# MotorController.net
KiCad netlist of a schematic drawn in Altium Designer
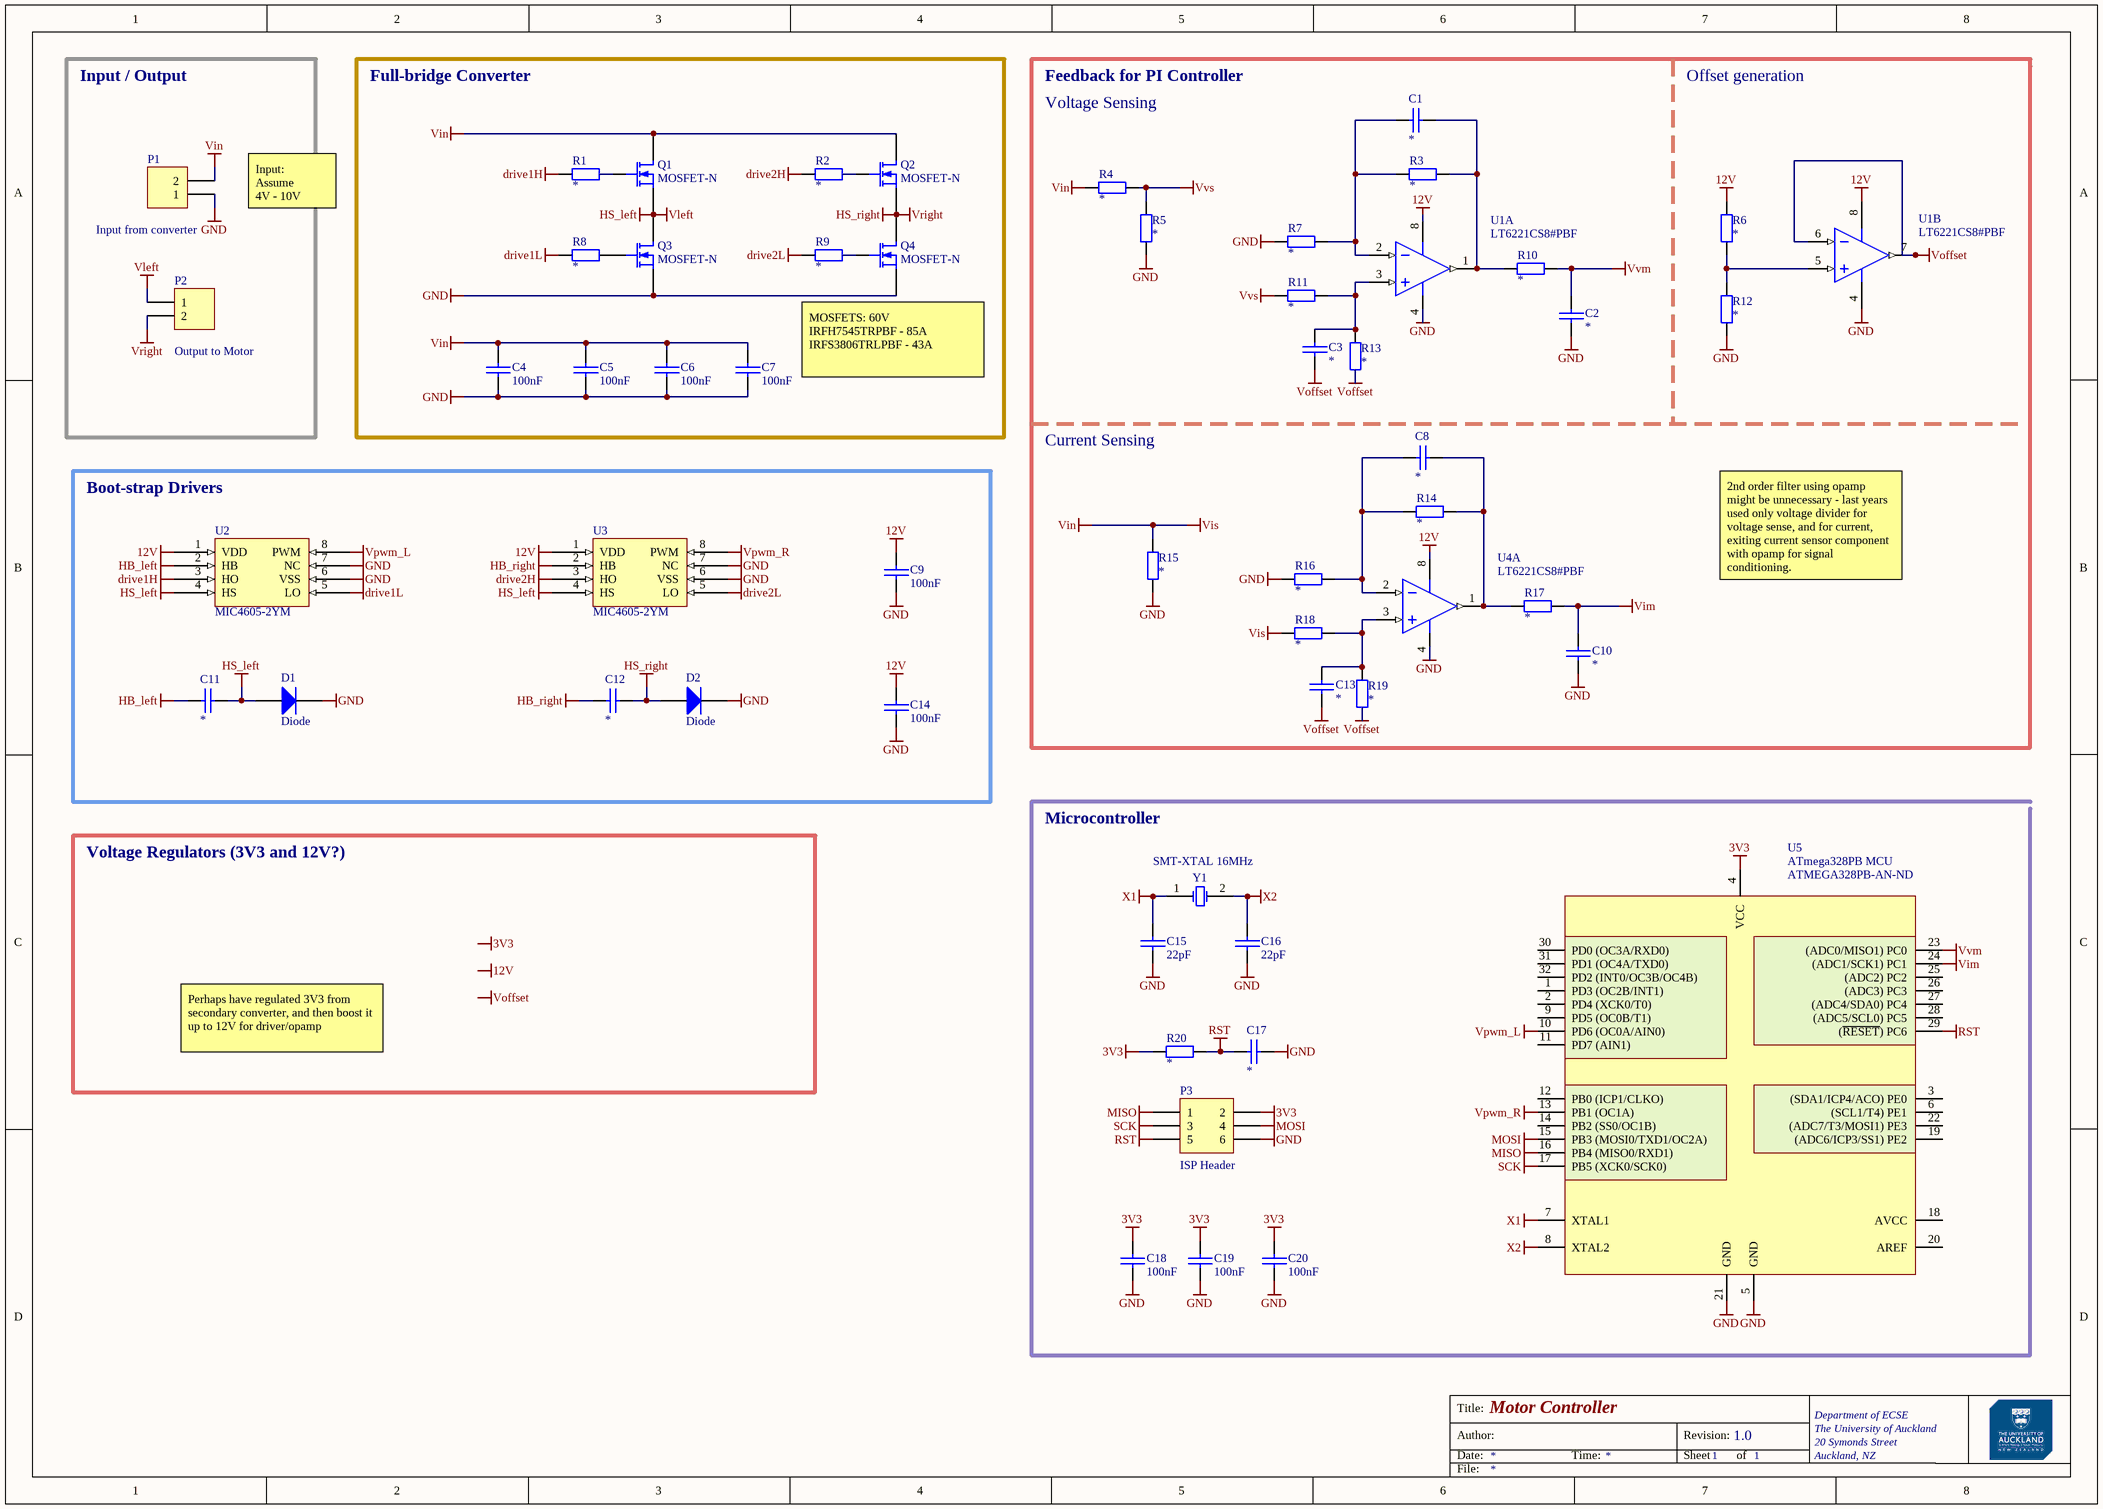
[diagram p0: MotorController.SchDoc]

(export (version "E")
  (design (tool "Eeschema 10.0.6"))
  (components
    (comp (ref "C1")
      (value "*")
      (footprint "0805 CAP")
      (description "SMT ceramic capacitor 0805 size")
      (libsource (lib "EE209_Library") (part "CerCap_SMT_0805"))
    )
    (comp (ref "C2")
      (value "*")
      (footprint "0805 CAP")
      (description "SMT ceramic capacitor 0805 size")
      (libsource (lib "EE209_Library") (part "CerCap_SMT_0805"))
    )
    (comp (ref "C3")
      (value "*")
      (footprint "0805 CAP")
      (description "SMT ceramic capacitor 0805 size")
      (libsource (lib "EE209_Library") (part "CerCap_SMT_0805"))
    )
    (comp (ref "C4")
      (value "100nF")
      (footprint "0805 CAP")
      (description "SMT ceramic capacitor 0805 size")
      (libsource (lib "EE209_Library") (part "CerCap_SMT_0805"))
    )
    (comp (ref "C5")
      (value "100nF")
      (footprint "0805 CAP")
      (description "SMT ceramic capacitor 0805 size")
      (libsource (lib "EE209_Library") (part "CerCap_SMT_0805"))
    )
    (comp (ref "C6")
      (value "100nF")
      (footprint "0805 CAP")
      (description "SMT ceramic capacitor 0805 size")
      (libsource (lib "EE209_Library") (part "CerCap_SMT_0805"))
    )
    (comp (ref "C7")
      (value "100nF")
      (footprint "0805 CAP")
      (description "SMT ceramic capacitor 0805 size")
      (libsource (lib "EE209_Library") (part "CerCap_SMT_0805"))
    )
    (comp (ref "C8")
      (value "*")
      (footprint "0805 CAP")
      (description "SMT ceramic capacitor 0805 size")
      (libsource (lib "EE209_Library") (part "CerCap_SMT_0805"))
    )
    (comp (ref "C9")
      (value "100nF")
      (footprint "0805 CAP")
      (description "SMT ceramic capacitor 0805 size")
      (libsource (lib "EE209_Library") (part "CerCap_SMT_0805"))
    )
    (comp (ref "C10")
      (value "*")
      (footprint "0805 CAP")
      (description "SMT ceramic capacitor 0805 size")
      (libsource (lib "EE209_Library") (part "CerCap_SMT_0805"))
    )
    (comp (ref "C11")
      (value "*")
      (footprint "0805 CAP")
      (description "SMT ceramic capacitor 0805 size")
      (libsource (lib "EE209_Library") (part "CerCap_SMT_0805"))
    )
    (comp (ref "C12")
      (value "*")
      (footprint "0805 CAP")
      (description "SMT ceramic capacitor 0805 size")
      (libsource (lib "EE209_Library") (part "CerCap_SMT_0805"))
    )
    (comp (ref "C13")
      (value "*")
      (footprint "0805 CAP")
      (description "SMT ceramic capacitor 0805 size")
      (libsource (lib "EE209_Library") (part "CerCap_SMT_0805"))
    )
    (comp (ref "C14")
      (value "100nF")
      (footprint "0805 CAP")
      (description "SMT ceramic capacitor 0805 size")
      (libsource (lib "EE209_Library") (part "CerCap_SMT_0805"))
    )
    (comp (ref "C15")
      (value "22pF")
      (footprint "0805 CAP")
      (description "SMT ceramic capacitor 0805 size")
      (libsource (lib "EE209_Library") (part "CerCap_SMT_0805"))
    )
    (comp (ref "C16")
      (value "22pF")
      (footprint "0805 CAP")
      (description "SMT ceramic capacitor 0805 size")
      (libsource (lib "EE209_Library") (part "CerCap_SMT_0805"))
    )
    (comp (ref "C17")
      (value "*")
      (footprint "0805 CAP")
      (description "SMT ceramic capacitor 0805 size")
      (libsource (lib "EE209_Library") (part "CerCap_SMT_0805"))
    )
    (comp (ref "C18")
      (value "100nF")
      (footprint "0805 CAP")
      (description "SMT ceramic capacitor 0805 size")
      (libsource (lib "EE209_Library") (part "CerCap_SMT_0805"))
    )
    (comp (ref "C19")
      (value "100nF")
      (footprint "0805 CAP")
      (description "SMT ceramic capacitor 0805 size")
      (libsource (lib "EE209_Library") (part "CerCap_SMT_0805"))
    )
    (comp (ref "C20")
      (value "100nF")
      (footprint "0805 CAP")
      (description "SMT ceramic capacitor 0805 size")
      (libsource (lib "EE209_Library") (part "CerCap_SMT_0805"))
    )
    (comp (ref "D1")
      (value "Diode")
      (footprint "SMC")
      (description "Default Diode")
      (fields (field (name "PUBLISHER") "Altium Limited"))
      (libsource (lib "Miscellaneous Devices") (part "Diode"))
    )
    (comp (ref "D2")
      (value "Diode")
      (footprint "SMC")
      (description "Default Diode")
      (fields (field (name "PUBLISHER") "Altium Limited"))
      (libsource (lib "Miscellaneous Devices") (part "Diode"))
    )
    (comp (ref "P1")
      (value "Input from converter")
      (footprint "HDR1X2H")
      (description "Header, 2-Pin, Right Angle")
      (fields (field (name "PUBLISHER") "Altium Limited"))
      (libsource (lib "") (part "Header 2H_1"))
    )
    (comp (ref "P2")
      (value "Output to Motor")
      (footprint "HDR1X2H")
      (description "Header, 2-Pin, Right Angle")
      (fields (field (name "PUBLISHER") "Altium Limited"))
      (libsource (lib "Miscellaneous Connectors") (part "Header 2H"))
    )
    (comp (ref "P3")
      (value "ISP Header")
      (footprint "HDR2X3")
      (description "Header, 3-Pin, Dual row")
      (fields (field (name "PUBLISHER") "Altium Limited"))
      (libsource (lib "Miscellaneous Connectors") (part "Header 3X2"))
    )
    (comp (ref "Q1")
      (value "MOSFET-N")
      (footprint "E3")
      (description "N-Channel MOSFET")
      (fields (field (name "PUBLISHER") "Altium Limited"))
      (libsource (lib "Miscellaneous Devices") (part "MOSFET-N"))
    )
    (comp (ref "Q2")
      (value "MOSFET-N")
      (footprint "E3")
      (description "N-Channel MOSFET")
      (fields (field (name "PUBLISHER") "Altium Limited"))
      (libsource (lib "Miscellaneous Devices") (part "MOSFET-N"))
    )
    (comp (ref "Q3")
      (value "MOSFET-N")
      (footprint "E3")
      (description "N-Channel MOSFET")
      (fields (field (name "PUBLISHER") "Altium Limited"))
      (libsource (lib "Miscellaneous Devices") (part "MOSFET-N"))
    )
    (comp (ref "Q4")
      (value "MOSFET-N")
      (footprint "E3")
      (description "N-Channel MOSFET")
      (fields (field (name "PUBLISHER") "Altium Limited"))
      (libsource (lib "Miscellaneous Devices") (part "MOSFET-N"))
    )
    (comp (ref "R1")
      (value "*")
      (footprint "0805 RES")
      (description "0805 resistor")
      (fields (field (name "PUBLISHER") "Altium Limited"))
      (libsource (lib "") (part "Res_SMT_0805_2"))
    )
    (comp (ref "R2")
      (value "*")
      (footprint "0805 RES")
      (description "0805 resistor")
      (fields (field (name "PUBLISHER") "Altium Limited"))
      (libsource (lib "") (part "Res_SMT_0805_2"))
    )
    (comp (ref "R3")
      (value "*")
      (footprint "0805 RES")
      (description "0805 resistor")
      (fields (field (name "PUBLISHER") "Altium Limited"))
      (libsource (lib "") (part "Res_SMT_0805_3"))
    )
    (comp (ref "R4")
      (value "*")
      (footprint "0805 RES")
      (description "0805 resistor")
      (fields (field (name "PUBLISHER") "Altium Limited"))
      (libsource (lib "") (part "Res_SMT_0805_3"))
    )
    (comp (ref "R5")
      (value "*")
      (footprint "0805 RES")
      (description "0805 resistor")
      (fields (field (name "PUBLISHER") "Altium Limited"))
      (libsource (lib "EE209_Library") (part "Res_SMT_0805"))
    )
    (comp (ref "R6")
      (value "*")
      (footprint "0805 RES")
      (description "0805 resistor")
      (fields (field (name "PUBLISHER") "Altium Limited"))
      (libsource (lib "") (part "Res_SMT_0805_1"))
    )
    (comp (ref "R7")
      (value "*")
      (footprint "0805 RES")
      (description "0805 resistor")
      (fields (field (name "PUBLISHER") "Altium Limited"))
      (libsource (lib "") (part "Res_SMT_0805_2"))
    )
    (comp (ref "R8")
      (value "*")
      (footprint "0805 RES")
      (description "0805 resistor")
      (fields (field (name "PUBLISHER") "Altium Limited"))
      (libsource (lib "") (part "Res_SMT_0805_2"))
    )
    (comp (ref "R9")
      (value "*")
      (footprint "0805 RES")
      (description "0805 resistor")
      (fields (field (name "PUBLISHER") "Altium Limited"))
      (libsource (lib "") (part "Res_SMT_0805_2"))
    )
    (comp (ref "R10")
      (value "*")
      (footprint "0805 RES")
      (description "0805 resistor")
      (fields (field (name "PUBLISHER") "Altium Limited"))
      (libsource (lib "") (part "Res_SMT_0805_3"))
    )
    (comp (ref "R11")
      (value "*")
      (footprint "0805 RES")
      (description "0805 resistor")
      (fields (field (name "PUBLISHER") "Altium Limited"))
      (libsource (lib "") (part "Res_SMT_0805_2"))
    )
    (comp (ref "R12")
      (value "*")
      (footprint "0805 RES")
      (description "0805 resistor")
      (fields (field (name "PUBLISHER") "Altium Limited"))
      (libsource (lib "") (part "Res_SMT_0805_1"))
    )
    (comp (ref "R13")
      (value "*")
      (footprint "0805 RES")
      (description "0805 resistor")
      (fields (field (name "PUBLISHER") "Altium Limited"))
      (libsource (lib "") (part "Res_SMT_0805_1"))
    )
    (comp (ref "R14")
      (value "*")
      (footprint "0805 RES")
      (description "0805 resistor")
      (fields (field (name "PUBLISHER") "Altium Limited"))
      (libsource (lib "") (part "Res_SMT_0805_3"))
    )
    (comp (ref "R15")
      (value "*")
      (footprint "0805 RES")
      (description "0805 resistor")
      (fields (field (name "PUBLISHER") "Altium Limited"))
      (libsource (lib "EE209_Library") (part "Res_SMT_0805"))
    )
    (comp (ref "R16")
      (value "*")
      (footprint "0805 RES")
      (description "0805 resistor")
      (fields (field (name "PUBLISHER") "Altium Limited"))
      (libsource (lib "") (part "Res_SMT_0805_2"))
    )
    (comp (ref "R17")
      (value "*")
      (footprint "0805 RES")
      (description "0805 resistor")
      (fields (field (name "PUBLISHER") "Altium Limited"))
      (libsource (lib "") (part "Res_SMT_0805_3"))
    )
    (comp (ref "R18")
      (value "*")
      (footprint "0805 RES")
      (description "0805 resistor")
      (fields (field (name "PUBLISHER") "Altium Limited"))
      (libsource (lib "") (part "Res_SMT_0805_2"))
    )
    (comp (ref "R19")
      (value "*")
      (footprint "0805 RES")
      (description "0805 resistor")
      (fields (field (name "PUBLISHER") "Altium Limited"))
      (libsource (lib "") (part "Res_SMT_0805_1"))
    )
    (comp (ref "R20")
      (value "*")
      (footprint "0805 RES")
      (description "0805 resistor")
      (fields (field (name "PUBLISHER") "Altium Limited"))
      (libsource (lib "") (part "Res_SMT_0805_3"))
    )
    (comp (ref "U1")
      (value "LT6221CS8#PBF")
      (footprint "LT-S8-8_N")
      (fields
        (field (name "LINEAR TECHNOLOGY PART NUMBER") "LT6221")
        (field (name "MANUFACTURER") "Linear Technology")
      )
      (libsource (lib "Altium Content Vault") (part "LT-LT6221-S8-8"))
    )
    (comp (ref "U2")
      (value "MIC4605-2YM")
      (description "Driver 1A 2-OUT High and Low Side Half Brdg Non-Inv 8-Pin SOIC N Tube")
      (fields
        (field (name "MANUFACTURER") "Microchip")
        (field (name "MANUFACTURER PART NUMBER") "MIC4605-2YM-T5")
      )
      (libsource (lib "SummerWorkshop") (part "MIC4605-2YM"))
    )
    (comp (ref "U3")
      (value "MIC4605-2YM")
      (description "Driver 1A 2-OUT High and Low Side Half Brdg Non-Inv 8-Pin SOIC N Tube")
      (fields
        (field (name "MANUFACTURER") "Microchip")
        (field (name "MANUFACTURER PART NUMBER") "MIC4605-2YM-T5")
      )
      (libsource (lib "SummerWorkshop") (part "MIC4605-2YM"))
    )
    (comp (ref "U4")
      (value "LT6221CS8#PBF")
      (footprint "LT-S8-8_N")
      (fields
        (field (name "LINEAR TECHNOLOGY PART NUMBER") "LT6221")
        (field (name "MANUFACTURER") "Linear Technology")
      )
      (libsource (lib "Altium Content Vault") (part "LT-LT6221-S8-8"))
    )
    (comp (ref "U5")
      (value "ATmega328PB MCU")
      (footprint "32 - TQFP")
      (description "IC MCU 8BIT 32KB FLASH 32TQFP")
      (fields
        (field (name "MANUFACTURER") "Atmel")
        (field (name "MANUFACTURER PART NUMBER") "ATMEGA328PB-AN")
        (field (name "SUPPLIER PART NUMBER 1") "ATMEGA328PB-AN-ND")
      )
      (libsource (lib "EE209_Library") (part "ATmega328PB_SMT_TQFP32"))
    )
    (comp (ref "Y1")
      (value "SMT-XTAL 16MHz")
      (footprint "HC49-US")
      (description "9C-16.000MAAJ-T crystal 16.0000MHZ 18PF SMD")
      (fields
        (field (name "MANUFACTURER") "TXC CORPORATION")
        (field (name "MANUFACTURER PART NUMBER") "9C-16.000MAAJ-T")
      )
      (libsource (lib "EE209_Library") (part "TXC9C-16_XTAL_SMT"))
    )
  )
  (nets
    (net (code "1") (name "3V3") (class "Default")
      (node (ref "C18") (pin "1") (pinfunction "1_1") (pintype "passive"))
      (node (ref "C19") (pin "1") (pinfunction "1_1") (pintype "passive"))
      (node (ref "C20") (pin "1") (pinfunction "1_1") (pintype "passive"))
      (node (ref "P3") (pin "2") (pinfunction "2_2") (pintype "passive"))
      (node (ref "R20") (pin "2") (pinfunction "2_2") (pintype "passive"))
      (node (ref "U5") (pin "4") (pinfunction "VCC_4") (pintype "passive"))
    )
    (net (code "2") (name "12V") (class "Default")
      (node (ref "C14") (pin "2") (pinfunction "2_2") (pintype "passive"))
      (node (ref "C9") (pin "2") (pinfunction "2_2") (pintype "passive"))
      (node (ref "R6") (pin "2") (pinfunction "2_2") (pintype "passive"))
      (node (ref "U1") (pin "8") (pinfunction "VS+_8") (pintype "power_in"))
      (node (ref "U2") (pin "1") (pinfunction "VDD_1") (pintype "input"))
      (node (ref "U3") (pin "1") (pinfunction "VDD_1") (pintype "input"))
      (node (ref "U4") (pin "8") (pinfunction "VS+_8") (pintype "power_in"))
    )
    (net (code "3") (name "GND") (class "Default")
      (node (ref "C10") (pin "1") (pinfunction "1_1") (pintype "passive"))
      (node (ref "C14") (pin "1") (pinfunction "1_1") (pintype "passive"))
      (node (ref "C15") (pin "2") (pinfunction "2_2") (pintype "passive"))
      (node (ref "C16") (pin "2") (pinfunction "2_2") (pintype "passive"))
      (node (ref "C17") (pin "2") (pinfunction "2_2") (pintype "passive"))
      (node (ref "C18") (pin "2") (pinfunction "2_2") (pintype "passive"))
      (node (ref "C19") (pin "2") (pinfunction "2_2") (pintype "passive"))
      (node (ref "C2") (pin "1") (pinfunction "1_1") (pintype "passive"))
      (node (ref "C20") (pin "2") (pinfunction "2_2") (pintype "passive"))
      (node (ref "C4") (pin "1") (pinfunction "1_1") (pintype "passive"))
      (node (ref "C5") (pin "1") (pinfunction "1_1") (pintype "passive"))
      (node (ref "C6") (pin "1") (pinfunction "1_1") (pintype "passive"))
      (node (ref "C7") (pin "1") (pinfunction "1_1") (pintype "passive"))
      (node (ref "C9") (pin "1") (pinfunction "1_1") (pintype "passive"))
      (node (ref "D1") (pin "2") (pinfunction "K_2") (pintype "passive"))
      (node (ref "D2") (pin "2") (pinfunction "K_2") (pintype "passive"))
      (node (ref "P1") (pin "1") (pinfunction "1_1") (pintype "passive"))
      (node (ref "P3") (pin "6") (pinfunction "6_6") (pintype "passive"))
      (node (ref "Q3") (pin "3") (pinfunction "S_3") (pintype "passive"))
      (node (ref "Q4") (pin "3") (pinfunction "S_3") (pintype "passive"))
      (node (ref "R12") (pin "1") (pinfunction "1_1") (pintype "passive"))
      (node (ref "R15") (pin "2") (pinfunction "2_2") (pintype "passive"))
      (node (ref "R16") (pin "1") (pinfunction "1_1") (pintype "passive"))
      (node (ref "R5") (pin "2") (pinfunction "2_2") (pintype "passive"))
      (node (ref "R7") (pin "1") (pinfunction "1_1") (pintype "passive"))
      (node (ref "U1") (pin "4") (pinfunction "VS-_4") (pintype "power_in"))
      (node (ref "U2") (pin "6") (pinfunction "VSS_6") (pintype "input"))
      (node (ref "U2") (pin "7") (pinfunction "NC_7") (pintype "input"))
      (node (ref "U3") (pin "6") (pinfunction "VSS_6") (pintype "input"))
      (node (ref "U3") (pin "7") (pinfunction "NC_7") (pintype "input"))
      (node (ref "U4") (pin "4") (pinfunction "VS-_4") (pintype "power_in"))
      (node (ref "U5") (pin "21") (pinfunction "GND_21") (pintype "passive"))
      (node (ref "U5") (pin "5") (pinfunction "GND_5") (pintype "passive"))
    )
    (net (code "4") (name "HB_left") (class "Default")
      (node (ref "C11") (pin "1") (pinfunction "1_1") (pintype "passive"))
      (node (ref "U2") (pin "2") (pinfunction "HB_2") (pintype "input"))
    )
    (net (code "5") (name "HB_right") (class "Default")
      (node (ref "C12") (pin "1") (pinfunction "1_1") (pintype "passive"))
      (node (ref "U3") (pin "2") (pinfunction "HB_2") (pintype "input"))
    )
    (net (code "6") (name "HS_left") (class "Default")
      (node (ref "C11") (pin "2") (pinfunction "2_2") (pintype "passive"))
      (node (ref "D1") (pin "1") (pinfunction "A_1") (pintype "passive"))
      (node (ref "P2") (pin "1") (pinfunction "1_1") (pintype "passive"))
      (node (ref "Q1") (pin "3") (pinfunction "S_3") (pintype "passive"))
      (node (ref "Q3") (pin "1") (pinfunction "D_1") (pintype "passive"))
      (node (ref "U2") (pin "4") (pinfunction "HS_4") (pintype "input"))
      (node (ref "U3") (pin "4") (pinfunction "HS_4") (pintype "input"))
    )
    (net (code "7") (name "HS_right") (class "Default")
      (node (ref "C12") (pin "2") (pinfunction "2_2") (pintype "passive"))
      (node (ref "D2") (pin "1") (pinfunction "A_1") (pintype "passive"))
      (node (ref "P2") (pin "2") (pinfunction "2_2") (pintype "passive"))
      (node (ref "Q2") (pin "3") (pinfunction "S_3") (pintype "passive"))
      (node (ref "Q4") (pin "1") (pinfunction "D_1") (pintype "passive"))
    )
    (net (code "8") (name "MISO") (class "Default")
      (node (ref "P3") (pin "1") (pinfunction "1_1") (pintype "passive"))
      (node (ref "U5") (pin "16") (pinfunction "PB4_(MISO0/RXD1)_16") (pintype "passive"))
    )
    (net (code "9") (name "MOSI") (class "Default")
      (node (ref "P3") (pin "4") (pinfunction "4_4") (pintype "passive"))
      (node (ref "U5") (pin "15") (pinfunction "PB3_(MOSI0/TXD1/OC2A)_15") (pintype "passive"))
    )
    (net (code "10") (name "Net-(Q1-G)") (class "Default")
      (node (ref "Q1") (pin "2") (pinfunction "G_2") (pintype "passive"))
      (node (ref "R1") (pin "2") (pinfunction "2_2") (pintype "passive"))
    )
    (net (code "11") (name "Net-(Q2-G)") (class "Default")
      (node (ref "Q2") (pin "2") (pinfunction "G_2") (pintype "passive"))
      (node (ref "R2") (pin "2") (pinfunction "2_2") (pintype "passive"))
    )
    (net (code "12") (name "Net-(Q4-G)") (class "Default")
      (node (ref "Q4") (pin "2") (pinfunction "G_2") (pintype "passive"))
      (node (ref "R9") (pin "2") (pinfunction "2_2") (pintype "passive"))
    )
    (net (code "13") (name "Net-(U1A-+IN_A)") (class "Default")
      (node (ref "C3") (pin "2") (pinfunction "2_2") (pintype "passive"))
      (node (ref "R11") (pin "2") (pinfunction "2_2") (pintype "passive"))
      (node (ref "R13") (pin "2") (pinfunction "2_2") (pintype "passive"))
      (node (ref "U1") (pin "3") (pinfunction "+IN_A_3") (pintype "input"))
    )
    (net (code "14") (name "Net-(U1A--IN_A)") (class "Default")
      (node (ref "C1") (pin "1") (pinfunction "1_1") (pintype "passive"))
      (node (ref "R3") (pin "2") (pinfunction "2_2") (pintype "passive"))
      (node (ref "R7") (pin "2") (pinfunction "2_2") (pintype "passive"))
      (node (ref "U1") (pin "2") (pinfunction "-IN_A_2") (pintype "input"))
    )
    (net (code "15") (name "Net-(U1A-OUT_A)") (class "Default")
      (node (ref "C1") (pin "2") (pinfunction "2_2") (pintype "passive"))
      (node (ref "R10") (pin "2") (pinfunction "2_2") (pintype "passive"))
      (node (ref "R3") (pin "1") (pinfunction "1_1") (pintype "passive"))
      (node (ref "U1") (pin "1") (pinfunction "OUT_A_1") (pintype "output"))
    )
    (net (code "16") (name "Net-(U1B-+IN_B)") (class "Default")
      (node (ref "R12") (pin "2") (pinfunction "2_2") (pintype "passive"))
      (node (ref "R6") (pin "1") (pinfunction "1_1") (pintype "passive"))
      (node (ref "U1") (pin "5") (pinfunction "+IN_B_5") (pintype "input"))
    )
    (net (code "17") (name "Net-(U4A-+IN_A)") (class "Default")
      (node (ref "C13") (pin "2") (pinfunction "2_2") (pintype "passive"))
      (node (ref "R18") (pin "2") (pinfunction "2_2") (pintype "passive"))
      (node (ref "R19") (pin "2") (pinfunction "2_2") (pintype "passive"))
      (node (ref "U4") (pin "3") (pinfunction "+IN_A_3") (pintype "input"))
    )
    (net (code "18") (name "Net-(U4A--IN_A)") (class "Default")
      (node (ref "C8") (pin "1") (pinfunction "1_1") (pintype "passive"))
      (node (ref "R14") (pin "2") (pinfunction "2_2") (pintype "passive"))
      (node (ref "R16") (pin "2") (pinfunction "2_2") (pintype "passive"))
      (node (ref "U4") (pin "2") (pinfunction "-IN_A_2") (pintype "input"))
    )
    (net (code "19") (name "Net-(U4A-OUT_A)") (class "Default")
      (node (ref "C8") (pin "2") (pinfunction "2_2") (pintype "passive"))
      (node (ref "R14") (pin "1") (pinfunction "1_1") (pintype "passive"))
      (node (ref "R17") (pin "2") (pinfunction "2_2") (pintype "passive"))
      (node (ref "U4") (pin "1") (pinfunction "OUT_A_1") (pintype "output"))
    )
    (net (code "20") (name "RST") (class "Default")
      (node (ref "C17") (pin "1") (pinfunction "1_1") (pintype "passive"))
      (node (ref "P3") (pin "5") (pinfunction "5_5") (pintype "passive"))
      (node (ref "R20") (pin "1") (pinfunction "1_1") (pintype "passive"))
      (node (ref "U5") (pin "29") (pinfunction "(~{RESET})_PC6_29") (pintype "passive"))
    )
    (net (code "21") (name "SCK") (class "Default")
      (node (ref "P3") (pin "3") (pinfunction "3_3") (pintype "passive"))
      (node (ref "U5") (pin "17") (pinfunction "PB5_(XCK0/SCK0)_17") (pintype "passive"))
    )
    (net (code "22") (name "Vim") (class "Default")
      (node (ref "C10") (pin "2") (pinfunction "2_2") (pintype "passive"))
      (node (ref "R17") (pin "1") (pinfunction "1_1") (pintype "passive"))
      (node (ref "U5") (pin "24") (pinfunction "(ADC1/SCK1)_PC1_24") (pintype "passive"))
    )
    (net (code "23") (name "Vin") (class "Default")
      (node (ref "C4") (pin "2") (pinfunction "2_2") (pintype "passive"))
      (node (ref "C5") (pin "2") (pinfunction "2_2") (pintype "passive"))
      (node (ref "C6") (pin "2") (pinfunction "2_2") (pintype "passive"))
      (node (ref "C7") (pin "2") (pinfunction "2_2") (pintype "passive"))
      (node (ref "P1") (pin "2") (pinfunction "2_2") (pintype "passive"))
      (node (ref "Q1") (pin "1") (pinfunction "D_1") (pintype "passive"))
      (node (ref "Q2") (pin "1") (pinfunction "D_1") (pintype "passive"))
      (node (ref "R15") (pin "1") (pinfunction "1_1") (pintype "passive"))
      (node (ref "R18") (pin "1") (pinfunction "1_1") (pintype "passive"))
      (node (ref "R4") (pin "2") (pinfunction "2_2") (pintype "passive"))
    )
    (net (code "24") (name "Voffset") (class "Default")
      (node (ref "C13") (pin "1") (pinfunction "1_1") (pintype "passive"))
      (node (ref "C3") (pin "1") (pinfunction "1_1") (pintype "passive"))
      (node (ref "R13") (pin "1") (pinfunction "1_1") (pintype "passive"))
      (node (ref "R19") (pin "1") (pinfunction "1_1") (pintype "passive"))
      (node (ref "U1") (pin "6") (pinfunction "-IN_B_6") (pintype "input"))
      (node (ref "U1") (pin "7") (pinfunction "OUT_B_7") (pintype "output"))
    )
    (net (code "25") (name "Vpwm_L") (class "Default")
      (node (ref "U2") (pin "8") (pinfunction "PWM_8") (pintype "input"))
      (node (ref "U5") (pin "10") (pinfunction "PD6_(OC0A/AIN0)_10") (pintype "passive"))
    )
    (net (code "26") (name "Vpwm_R") (class "Default")
      (node (ref "U3") (pin "8") (pinfunction "PWM_8") (pintype "input"))
      (node (ref "U5") (pin "13") (pinfunction "PB1_(OC1A)_13") (pintype "passive"))
    )
    (net (code "27") (name "Vvm") (class "Default")
      (node (ref "C2") (pin "2") (pinfunction "2_2") (pintype "passive"))
      (node (ref "R10") (pin "1") (pinfunction "1_1") (pintype "passive"))
      (node (ref "U5") (pin "23") (pinfunction "(ADC0/MISO1)_PC0_23") (pintype "passive"))
    )
    (net (code "28") (name "Vvs") (class "Default")
      (node (ref "R11") (pin "1") (pinfunction "1_1") (pintype "passive"))
      (node (ref "R4") (pin "1") (pinfunction "1_1") (pintype "passive"))
      (node (ref "R5") (pin "1") (pinfunction "1_1") (pintype "passive"))
    )
    (net (code "29") (name "X1") (class "Default")
      (node (ref "C15") (pin "1") (pinfunction "1_1") (pintype "passive"))
      (node (ref "U5") (pin "7") (pinfunction "XTAL1_7") (pintype "passive"))
      (node (ref "Y1") (pin "1") (pinfunction "OSC1_1") (pintype "passive"))
    )
    (net (code "30") (name "X2") (class "Default")
      (node (ref "C16") (pin "1") (pinfunction "1_1") (pintype "passive"))
      (node (ref "U5") (pin "8") (pinfunction "XTAL2_8") (pintype "passive"))
      (node (ref "Y1") (pin "2") (pinfunction "OSC2_2") (pintype "passive"))
    )
    (net (code "31") (name "drive1H") (class "Default")
      (node (ref "R1") (pin "1") (pinfunction "1_1") (pintype "passive"))
      (node (ref "U2") (pin "3") (pinfunction "HO_3") (pintype "input"))
    )
    (net (code "32") (name "drive1L") (class "Default")
      (node (ref "R8") (pin "1") (pinfunction "1_1") (pintype "passive"))
      (node (ref "U2") (pin "5") (pinfunction "LO_5") (pintype "input"))
    )
    (net (code "33") (name "drive2H") (class "Default")
      (node (ref "R2") (pin "1") (pinfunction "1_1") (pintype "passive"))
      (node (ref "U3") (pin "3") (pinfunction "HO_3") (pintype "input"))
    )
    (net (code "34") (name "drive2L") (class "Default")
      (node (ref "R9") (pin "1") (pinfunction "1_1") (pintype "passive"))
      (node (ref "U3") (pin "5") (pinfunction "LO_5") (pintype "input"))
    )
    (net (code "35") (name "unconnected-(Q3-G-Pad2)") (class "Default")
      (node (ref "Q3") (pin "2") (pinfunction "G_2") (pintype "passive"))
    )
    (net (code "36") (name "unconnected-(R8-Pad2)") (class "Default")
      (node (ref "R8") (pin "2") (pinfunction "2_2") (pintype "passive"))
    )
    (net (code "37") (name "unconnected-(U5-(ADC2)_PC2-Pad25)") (class "Default")
      (node (ref "U5") (pin "25") (pinfunction "(ADC2)_PC2_25") (pintype "passive"))
    )
    (net (code "38") (name "unconnected-(U5-(ADC3)_PC3-Pad26)") (class "Default")
      (node (ref "U5") (pin "26") (pinfunction "(ADC3)_PC3_26") (pintype "passive"))
    )
    (net (code "39") (name "unconnected-(U5-(ADC4{slash}SDA0)_PC4-Pad27)") (class "Default")
      (node (ref "U5") (pin "27") (pinfunction "(ADC4/SDA0)_PC4_27") (pintype "passive"))
    )
    (net (code "40") (name "unconnected-(U5-(ADC5{slash}SCL0)_PC5-Pad28)") (class "Default")
      (node (ref "U5") (pin "28") (pinfunction "(ADC5/SCL0)_PC5_28") (pintype "passive"))
    )
    (net (code "41") (name "unconnected-(U5-(ADC6{slash}ICP3{slash}SS1)_PE2-Pad19)") (class "Default")
      (node (ref "U5") (pin "19") (pinfunction "(ADC6/ICP3/SS1)_PE2_19") (pintype "passive"))
    )
    (net (code "42") (name "unconnected-(U5-(ADC7{slash}T3{slash}MOSI1)_PE3-Pad22)") (class "Default")
      (node (ref "U5") (pin "22") (pinfunction "(ADC7/T3/MOSI1)_PE3_22") (pintype "passive"))
    )
    (net (code "43") (name "unconnected-(U5-(SCL1{slash}T4)_PE1-Pad6)") (class "Default")
      (node (ref "U5") (pin "6") (pinfunction "(SCL1/T4)_PE1_6") (pintype "passive"))
    )
    (net (code "44") (name "unconnected-(U5-(SDA1{slash}ICP4{slash}ACO)_PE0-Pad3)") (class "Default")
      (node (ref "U5") (pin "3") (pinfunction "(SDA1/ICP4/ACO)_PE0_3") (pintype "passive"))
    )
    (net (code "45") (name "unconnected-(U5-AREF-Pad20)") (class "Default")
      (node (ref "U5") (pin "20") (pinfunction "AREF_20") (pintype "passive"))
    )
    (net (code "46") (name "unconnected-(U5-AVCC-Pad18)") (class "Default")
      (node (ref "U5") (pin "18") (pinfunction "AVCC_18") (pintype "passive"))
    )
    (net (code "47") (name "unconnected-(U5-PB0_(ICP1{slash}CLKO)-Pad12)") (class "Default")
      (node (ref "U5") (pin "12") (pinfunction "PB0_(ICP1/CLKO)_12") (pintype "passive"))
    )
    (net (code "48") (name "unconnected-(U5-PB2_(SS0{slash}OC1B)-Pad14)") (class "Default")
      (node (ref "U5") (pin "14") (pinfunction "PB2_(SS0/OC1B)_14") (pintype "passive"))
    )
    (net (code "49") (name "unconnected-(U5-PD0_(OC3A{slash}RXD0)-Pad30)") (class "Default")
      (node (ref "U5") (pin "30") (pinfunction "PD0_(OC3A/RXD0)_30") (pintype "passive"))
    )
    (net (code "50") (name "unconnected-(U5-PD1_(OC4A{slash}TXD0)-Pad31)") (class "Default")
      (node (ref "U5") (pin "31") (pinfunction "PD1_(OC4A/TXD0)_31") (pintype "passive"))
    )
    (net (code "51") (name "unconnected-(U5-PD2_(INT0{slash}OC3B{slash}OC4B)-Pad32)") (class "Default")
      (node (ref "U5") (pin "32") (pinfunction "PD2_(INT0/OC3B/OC4B)_32") (pintype "passive"))
    )
    (net (code "52") (name "unconnected-(U5-PD3_(OC2B{slash}INT1)-Pad1)") (class "Default")
      (node (ref "U5") (pin "1") (pinfunction "PD3_(OC2B/INT1)_1") (pintype "passive"))
    )
    (net (code "53") (name "unconnected-(U5-PD4_(XCK0{slash}T0)-Pad2)") (class "Default")
      (node (ref "U5") (pin "2") (pinfunction "PD4_(XCK0/T0)_2") (pintype "passive"))
    )
    (net (code "54") (name "unconnected-(U5-PD5_(OC0B{slash}T1)-Pad9)") (class "Default")
      (node (ref "U5") (pin "9") (pinfunction "PD5_(OC0B/T1)_9") (pintype "passive"))
    )
    (net (code "55") (name "unconnected-(U5-PD7_(AIN1)-Pad11)") (class "Default")
      (node (ref "U5") (pin "11") (pinfunction "PD7_(AIN1)_11") (pintype "passive"))
    )
  )
)
